# nrf24l01_cell.net
KiCad netlist of a schematic drawn in Altium Designer
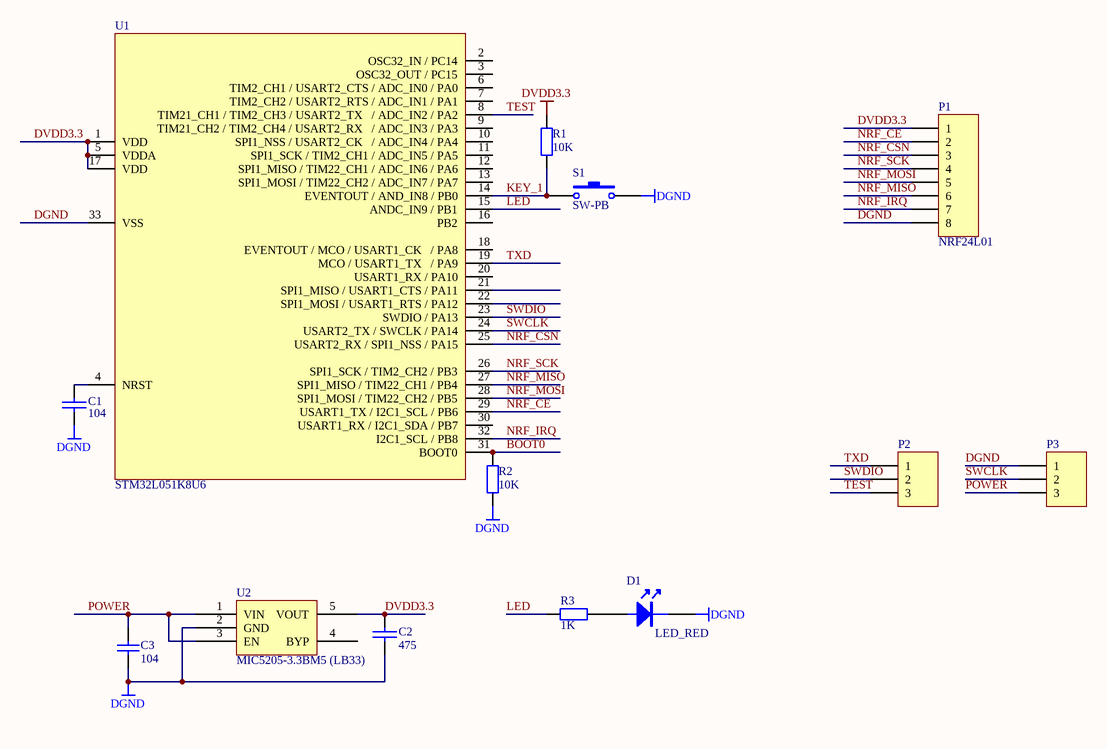
[diagram p0: nrf24l01_cell.SchDoc]

(export (version "E")
  (design (tool "Eeschema 10.0.6"))
  (components
    (comp (ref "C1")
      (value "104")
      (footprint "1608(0603C)")
      (description "Capacitor")
      (libsource (lib "*") (part "CAP"))
    )
    (comp (ref "C2")
      (value "475")
      (footprint "1608(0603C)")
      (description "Capacitor")
      (libsource (lib "*") (part "CAP"))
    )
    (comp (ref "C3")
      (value "104")
      (footprint "1608(0603C)")
      (description "Capacitor")
      (fields (field (name "PUBLISHER") "Altium Limited"))
      (libsource (lib "Miscellaneous Devices") (part "Cap"))
    )
    (comp (ref "D1") (value "LED_RED") (footprint "LED-0603R") (libsource (lib "*") (part "LED")))
    (comp (ref "P1")
      (value "NRF24L01")
      (footprint "SSSIP8X_N")
      (description "Header, 8-Pin")
      (fields (field (name "PUBLISHER") "Altium Limited"))
      (libsource (lib "Miscellaneous Connectors") (part "Header 8"))
    )
    (comp (ref "P2")
      (value "~")
      (footprint "SIPP3X")
      (description "Header, 3-Pin")
      (fields (field (name "PUBLISHER") "Altium Limited"))
      (libsource (lib "Miscellaneous Connectors") (part "Header 3"))
    )
    (comp (ref "P3")
      (value "~")
      (footprint "SIPP3X")
      (description "Header, 3-Pin")
      (fields (field (name "PUBLISHER") "Altium Limited"))
      (libsource (lib "Miscellaneous Connectors") (part "Header 3"))
    )
    (comp (ref "R1")
      (value "10K")
      (footprint "1608(0603R)")
      (description "Resistor")
      (fields (field (name "PUBLISHER") "Altium Limited"))
      (libsource (lib "Miscellaneous Devices") (part "Res2"))
    )
    (comp (ref "R2")
      (value "10K")
      (footprint "1608(0603R)")
      (description "Resistor")
      (fields (field (name "PUBLISHER") "Altium Limited"))
      (libsource (lib "Miscellaneous Devices") (part "Res2"))
    )
    (comp (ref "R3")
      (value "1K")
      (footprint "1608(0603R)")
      (description "Resistor")
      (fields (field (name "PUBLISHER") "Altium Limited"))
      (libsource (lib "") (part "Res2_1"))
    )
    (comp (ref "S1")
      (value "SW-PB")
      (footprint "KEY-3")
      (description "Switch")
      (fields (field (name "PUBLISHER") "Altium Limited"))
      (libsource (lib "Miscellaneous Devices") (part "SW-PB"))
    )
    (comp (ref "U1") (value "STM32L051K8U6") (libsource (lib "MySCH") (part "STM32L051K8U6")))
    (comp (ref "U2")
      (value "MIC5205-3.3BM5 (LB33)")
      (footprint "SOT23-5")
      (libsource (lib "power") (part "MIC5205"))
    )
  )
  (nets
    (net (code "1") (name "/BOOT0") (class "Default")
      (node (ref "R2") (pin "1") (pinfunction "1_1") (pintype "passive"))
      (node (ref "U1") (pin "31") (pinfunction "BOOT0_31") (pintype "passive"))
    )
    (net (code "2") (name "/KEY_1") (class "Default")
      (node (ref "R1") (pin "2") (pinfunction "2_2") (pintype "passive"))
      (node (ref "S1") (pin "2") (pinfunction "2_2") (pintype "passive"))
      (node (ref "U1") (pin "14") (pinfunction "EVENTOUT_/_AND_IN8_/_PB0_14") (pintype "passive"))
    )
    (net (code "3") (name "/LED") (class "Default")
      (node (ref "R3") (pin "1") (pinfunction "1_1") (pintype "passive"))
      (node (ref "U1") (pin "15") (pinfunction "ANDC_IN9_/_PB1_15") (pintype "passive"))
    )
    (net (code "4") (name "/NRF_CE") (class "Default")
      (node (ref "P1") (pin "2") (pinfunction "2_2") (pintype "passive"))
      (node (ref "U1") (pin "29") (pinfunction "USART1_TX_/_I2C1_SCL_/_PB6_29") (pintype "passive"))
    )
    (net (code "5") (name "/NRF_CSN") (class "Default")
      (node (ref "P1") (pin "3") (pinfunction "3_3") (pintype "passive"))
      (node (ref "U1") (pin "25") (pinfunction "USART2_RX_/_SPI1_NSS_/_PA15_25") (pintype "passive"))
    )
    (net (code "6") (name "/NRF_IRQ") (class "Default")
      (node (ref "P1") (pin "7") (pinfunction "7_7") (pintype "passive"))
      (node (ref "U1") (pin "32") (pinfunction "I2C1_SCL_/_PB8_32") (pintype "passive"))
    )
    (net (code "7") (name "/NRF_MISO") (class "Default")
      (node (ref "P1") (pin "6") (pinfunction "6_6") (pintype "passive"))
      (node (ref "U1") (pin "27") (pinfunction "SPI1_MISO_/_TIM22_CH1_/_PB4_27") (pintype "passive"))
    )
    (net (code "8") (name "/NRF_MOSI") (class "Default")
      (node (ref "P1") (pin "5") (pinfunction "5_5") (pintype "passive"))
      (node (ref "U1") (pin "28") (pinfunction "SPI1_MOSI_/_TIM22_CH2_/_PB5_28") (pintype "passive"))
    )
    (net (code "9") (name "/NRF_SCK") (class "Default")
      (node (ref "P1") (pin "4") (pinfunction "4_4") (pintype "passive"))
      (node (ref "U1") (pin "26") (pinfunction "SPI1_SCK_/_TIM2_CH2_/_PB3_26") (pintype "passive"))
    )
    (net (code "10") (name "/POWER") (class "Default")
      (node (ref "C3") (pin "2") (pinfunction "2_2") (pintype "passive"))
      (node (ref "P3") (pin "3") (pinfunction "3_3") (pintype "passive"))
      (node (ref "U2") (pin "1") (pinfunction "VIN_1") (pintype "passive"))
      (node (ref "U2") (pin "3") (pinfunction "EN_3") (pintype "passive"))
    )
    (net (code "11") (name "/SWCLK") (class "Default")
      (node (ref "P3") (pin "2") (pinfunction "2_2") (pintype "passive"))
      (node (ref "U1") (pin "24") (pinfunction "USART2_TX_/_SWCLK_/_PA14_24") (pintype "passive"))
    )
    (net (code "12") (name "/SWDIO") (class "Default")
      (node (ref "P2") (pin "2") (pinfunction "2_2") (pintype "passive"))
      (node (ref "U1") (pin "23") (pinfunction "SWDIO_/_PA13_23") (pintype "passive"))
    )
    (net (code "13") (name "/TEST") (class "Default")
      (node (ref "P2") (pin "3") (pinfunction "3_3") (pintype "passive"))
      (node (ref "U1") (pin "8") (pinfunction "TIM21_CH1_/_TIM2_CH3_/_USART2_TX___/_ADC_IN2_/_PA2_8") (pintype "passive"))
    )
    (net (code "14") (name "/TXD") (class "Default")
      (node (ref "P2") (pin "1") (pinfunction "1_1") (pintype "passive"))
      (node (ref "U1") (pin "19") (pinfunction "MCO_/_USART1_TX___/_PA9_19") (pintype "passive"))
    )
    (net (code "15") (name "DGND") (class "Default")
      (node (ref "C1") (pin "2") (pinfunction "2_2") (pintype "passive"))
      (node (ref "C2") (pin "2") (pinfunction "2_2") (pintype "passive"))
      (node (ref "C3") (pin "1") (pinfunction "1_1") (pintype "passive"))
      (node (ref "D1") (pin "K") (pinfunction "2_K") (pintype "passive"))
      (node (ref "P1") (pin "8") (pinfunction "8_8") (pintype "passive"))
      (node (ref "P3") (pin "1") (pinfunction "1_1") (pintype "passive"))
      (node (ref "R2") (pin "2") (pinfunction "2_2") (pintype "passive"))
      (node (ref "S1") (pin "1") (pinfunction "1_1") (pintype "passive"))
      (node (ref "U1") (pin "33") (pinfunction "VSS_33") (pintype "passive"))
      (node (ref "U2") (pin "2") (pinfunction "GND_2") (pintype "passive"))
    )
    (net (code "16") (name "DVDD3.3") (class "Default")
      (node (ref "C2") (pin "1") (pinfunction "1_1") (pintype "passive"))
      (node (ref "P1") (pin "1") (pinfunction "1_1") (pintype "passive"))
      (node (ref "R1") (pin "1") (pinfunction "1_1") (pintype "passive"))
      (node (ref "U1") (pin "1") (pinfunction "VDD_1") (pintype "passive"))
      (node (ref "U1") (pin "17") (pinfunction "VDD_17") (pintype "passive"))
      (node (ref "U1") (pin "5") (pinfunction "VDDA_5") (pintype "passive"))
      (node (ref "U2") (pin "5") (pinfunction "VOUT_5") (pintype "passive"))
    )
    (net (code "17") (name "Net-(D1-1)") (class "Default")
      (node (ref "D1") (pin "A") (pinfunction "1_A") (pintype "passive"))
      (node (ref "R3") (pin "2") (pinfunction "2_2") (pintype "passive"))
    )
    (net (code "18") (name "Net-(U1-NRST)") (class "Default")
      (node (ref "C1") (pin "1") (pinfunction "1_1") (pintype "passive"))
      (node (ref "U1") (pin "4") (pinfunction "NRST_4") (pintype "passive"))
    )
    (net (code "19") (name "unconnected-(U1-EVENTOUT_{slash}_MCO_{slash}_USART1_CK___{slash}_PA8-Pad18)") (class "Default")
      (node (ref "U1") (pin "18") (pinfunction "EVENTOUT_/_MCO_/_USART1_CK___/_PA8_18") (pintype "passive"))
    )
    (net (code "20") (name "unconnected-(U1-OSC32_IN_{slash}_PC14-Pad2)") (class "Default")
      (node (ref "U1") (pin "2") (pinfunction "OSC32_IN_/_PC14_2") (pintype "passive"))
    )
    (net (code "21") (name "unconnected-(U1-OSC32_OUT_{slash}_PC15-Pad3)") (class "Default")
      (node (ref "U1") (pin "3") (pinfunction "OSC32_OUT_/_PC15_3") (pintype "passive"))
    )
    (net (code "22") (name "unconnected-(U1-PB2-Pad16)") (class "Default")
      (node (ref "U1") (pin "16") (pinfunction "PB2_16") (pintype "passive"))
    )
    (net (code "23") (name "unconnected-(U1-SPI1_MISO_{slash}_TIM22_CH1_{slash}_ADC_IN6_{slash}_PA6-Pad12)") (class "Default")
      (node (ref "U1") (pin "12") (pinfunction "SPI1_MISO_/_TIM22_CH1_/_ADC_IN6_/_PA6_12") (pintype "passive"))
    )
    (net (code "24") (name "unconnected-(U1-SPI1_MISO_{slash}_USART1_CTS_{slash}_PA11-Pad21)") (class "Default")
      (node (ref "U1") (pin "21") (pinfunction "SPI1_MISO_/_USART1_CTS_/_PA11_21") (pintype "passive"))
    )
    (net (code "25") (name "unconnected-(U1-SPI1_MOSI_{slash}_TIM22_CH2_{slash}_ADC_IN7_{slash}_PA7-Pad13)") (class "Default")
      (node (ref "U1") (pin "13") (pinfunction "SPI1_MOSI_/_TIM22_CH2_/_ADC_IN7_/_PA7_13") (pintype "passive"))
    )
    (net (code "26") (name "unconnected-(U1-SPI1_MOSI_{slash}_USART1_RTS_{slash}_PA12-Pad22)") (class "Default")
      (node (ref "U1") (pin "22") (pinfunction "SPI1_MOSI_/_USART1_RTS_/_PA12_22") (pintype "passive"))
    )
    (net (code "27") (name "unconnected-(U1-SPI1_NSS_{slash}_USART2_CK___{slash}_ADC_IN4_{slash}_PA4-Pad10)") (class "Default")
      (node (ref "U1") (pin "10") (pinfunction "SPI1_NSS_/_USART2_CK___/_ADC_IN4_/_PA4_10") (pintype "passive"))
    )
    (net (code "28") (name "unconnected-(U1-SPI1_SCK_{slash}_TIM2_CH1_{slash}_ADC_IN5_{slash}_PA5-Pad11)") (class "Default")
      (node (ref "U1") (pin "11") (pinfunction "SPI1_SCK_/_TIM2_CH1_/_ADC_IN5_/_PA5_11") (pintype "passive"))
    )
    (net (code "29") (name "unconnected-(U1-TIM2_CH1_{slash}_USART2_CTS_{slash}_ADC_IN0_{slash}_PA0-Pad6)") (class "Default")
      (node (ref "U1") (pin "6") (pinfunction "TIM2_CH1_/_USART2_CTS_/_ADC_IN0_/_PA0_6") (pintype "passive"))
    )
    (net (code "30") (name "unconnected-(U1-TIM2_CH2_{slash}_USART2_RTS_{slash}_ADC_IN1_{slash}_PA1-Pad7)") (class "Default")
      (node (ref "U1") (pin "7") (pinfunction "TIM2_CH2_/_USART2_RTS_/_ADC_IN1_/_PA1_7") (pintype "passive"))
    )
    (net (code "31") (name "unconnected-(U1-TIM21_CH2_{slash}_TIM2_CH4_{slash}_USART2_RX___{slash}_ADC_IN3_{slash}_PA3-Pad9)") (class "Default")
      (node (ref "U1") (pin "9") (pinfunction "TIM21_CH2_/_TIM2_CH4_/_USART2_RX___/_ADC_IN3_/_PA3_9") (pintype "passive"))
    )
    (net (code "32") (name "unconnected-(U1-USART1_RX_{slash}_I2C1_SDA_{slash}_PB7-Pad30)") (class "Default")
      (node (ref "U1") (pin "30") (pinfunction "USART1_RX_/_I2C1_SDA_/_PB7_30") (pintype "passive"))
    )
    (net (code "33") (name "unconnected-(U1-USART1_RX_{slash}_PA10-Pad20)") (class "Default")
      (node (ref "U1") (pin "20") (pinfunction "USART1_RX_/_PA10_20") (pintype "passive"))
    )
    (net (code "34") (name "unconnected-(U2-BYP-Pad4)") (class "Default")
      (node (ref "U2") (pin "4") (pinfunction "BYP_4") (pintype "passive"))
    )
  )
)
